# ESP32_AC_dimmer_10ch_r1.net
KiCad netlist of a schematic drawn in EAGLE
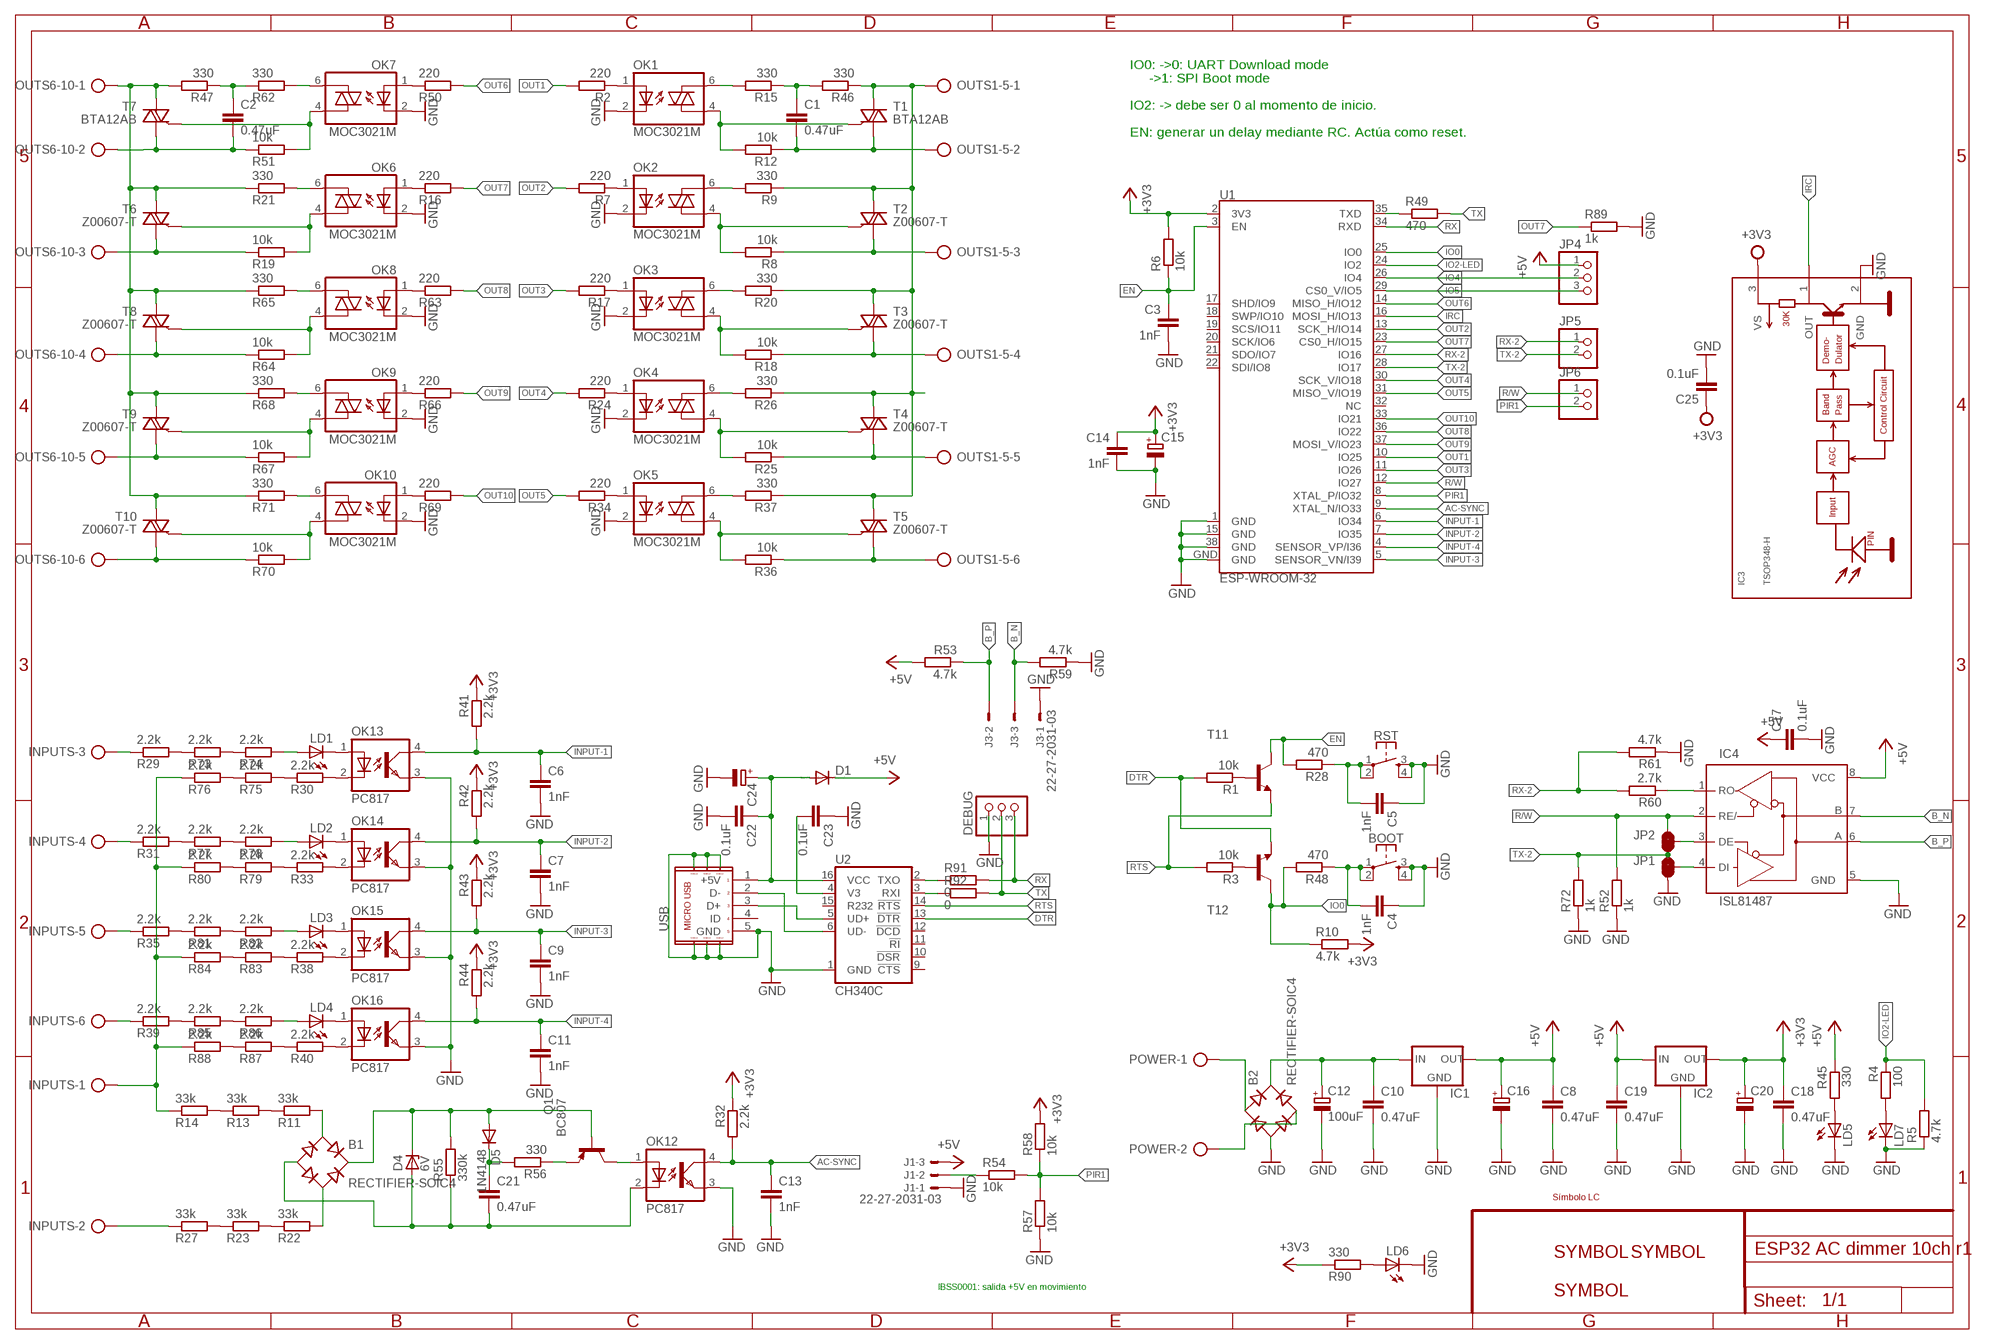
[diagram p0: schematic, sheet 1]

(export (version "E")
  (design (tool "Eeschema 10.0.6"))
  (components
    (comp (ref "B1")
      (value "RECTIFIER-SOIC4")
      (footprint "eagle-import:SOIC4")
      (libsource (lib "eagle-import") (part "RECTIFIER-SOIC4"))
    )
    (comp (ref "B2")
      (value "RECTIFIER-SOIC4")
      (footprint "eagle-import:SOIC4")
      (libsource (lib "eagle-import") (part "RECTIFIER-SOIC4"))
    )
    (comp (ref "BOOT")
      (value "MOMENTARY-SWITCH-SPST-2-SMD-4.6X2.8MM")
      (footprint "eagle-import:TACTILE_SWITCH_SMD_4.6X2.8MM")
      (libsource (lib "eagle-import") (part "MOMENTARY-SWITCH-SPST-2-SMD-4.6X2.8MM"))
    )
    (comp (ref "C1")
      (value "0.47uF")
      (footprint "eagle-import:C075-042X103")
      (libsource (lib "eagle-import") (part "C-EU075-042X103"))
    )
    (comp (ref "C2")
      (value "0.47uF")
      (footprint "eagle-import:C075-042X103")
      (libsource (lib "eagle-import") (part "C-EU075-042X103"))
    )
    (comp (ref "C3")
      (value "1nF")
      (footprint "eagle-import:C0603")
      (libsource (lib "eagle-import") (part "C-EUC0603"))
    )
    (comp (ref "C4")
      (value "1nF")
      (footprint "eagle-import:C0603")
      (libsource (lib "eagle-import") (part "C-EUC0603"))
    )
    (comp (ref "C5")
      (value "1nF")
      (footprint "eagle-import:C0603")
      (libsource (lib "eagle-import") (part "C-EUC0603"))
    )
    (comp (ref "C6")
      (value "1nF")
      (footprint "eagle-import:C0603")
      (libsource (lib "eagle-import") (part "C-EUC0603"))
    )
    (comp (ref "C7")
      (value "1nF")
      (footprint "eagle-import:C0603")
      (libsource (lib "eagle-import") (part "C-EUC0603"))
    )
    (comp (ref "C8")
      (value "0.47uF")
      (footprint "eagle-import:C0805")
      (libsource (lib "eagle-import") (part "C-EUC0805"))
    )
    (comp (ref "C9")
      (value "1nF")
      (footprint "eagle-import:C0603")
      (libsource (lib "eagle-import") (part "C-EUC0603"))
    )
    (comp (ref "C10")
      (value "0.47uF")
      (footprint "eagle-import:C0805")
      (libsource (lib "eagle-import") (part "C-EUC0805"))
    )
    (comp (ref "C11")
      (value "1nF")
      (footprint "eagle-import:C0603")
      (libsource (lib "eagle-import") (part "C-EUC0603"))
    )
    (comp (ref "C12")
      (value "100uF")
      (footprint "eagle-import:E3,5-8")
      (libsource (lib "eagle-import") (part "CPOL-EUE3.5-8"))
    )
    (comp (ref "C13")
      (value "1nF")
      (footprint "eagle-import:C0603")
      (libsource (lib "eagle-import") (part "C-EUC0603"))
    )
    (comp (ref "C14")
      (value "1nF")
      (footprint "eagle-import:C0805")
      (libsource (lib "eagle-import") (part "C-EUC0805"))
    )
    (comp (ref "C15")
      (value "CPOL-EUSMCA")
      (footprint "eagle-import:SMC_A")
      (libsource (lib "eagle-import") (part "rcl_334_CPOL-EUSMCA"))
    )
    (comp (ref "C16")
      (value "CPOL-EUSMCA")
      (footprint "eagle-import:SMC_A")
      (libsource (lib "eagle-import") (part "rcl_334_CPOL-EUSMCA"))
    )
    (comp (ref "C17")
      (value "0.1uF")
      (footprint "eagle-import:RCL_C0603")
      (libsource (lib "eagle-import") (part "RCL_C-EUC0603"))
    )
    (comp (ref "C18")
      (value "0.47uF")
      (footprint "eagle-import:C0805")
      (libsource (lib "eagle-import") (part "C-EUC0805"))
    )
    (comp (ref "C19")
      (value "0.47uF")
      (footprint "eagle-import:C0805")
      (libsource (lib "eagle-import") (part "C-EUC0805"))
    )
    (comp (ref "C20")
      (value "CPOL-EUSMCA")
      (footprint "eagle-import:SMC_A")
      (libsource (lib "eagle-import") (part "rcl_334_CPOL-EUSMCA"))
    )
    (comp (ref "C21")
      (value "0.47uF")
      (footprint "eagle-import:C0805")
      (libsource (lib "eagle-import") (part "C-EUC0805"))
    )
    (comp (ref "C22")
      (value "0.1uF")
      (footprint "eagle-import:C0603")
      (libsource (lib "eagle-import") (part "C-EUC0603"))
    )
    (comp (ref "C23")
      (value "0.1uF")
      (footprint "eagle-import:C0603")
      (libsource (lib "eagle-import") (part "C-EUC0603"))
    )
    (comp (ref "C24")
      (value "CPOL-EUSMCA")
      (footprint "eagle-import:SMC_A")
      (libsource (lib "eagle-import") (part "rcl_334_CPOL-EUSMCA"))
    )
    (comp (ref "C25")
      (value "0.1uF")
      (footprint "eagle-import:C0603")
      (libsource (lib "eagle-import") (part "C-EUC0603"))
    )
    (comp (ref "D1")
      (value "DIODE-SOD323-R")
      (footprint "eagle-import:SOD323-R")
      (libsource (lib "eagle-import") (part "diode_210_DIODE-SOD323-R"))
    )
    (comp (ref "D4")
      (value "6V")
      (footprint "eagle-import:SOD80C")
      (libsource (lib "eagle-import") (part "ZENER-DIODESOD80C"))
    )
    (comp (ref "D5")
      (value "1N4148")
      (footprint "eagle-import:MINIMELF")
      (libsource (lib "eagle-import") (part "DIODE-MINIMELF"))
    )
    (comp (ref "DEBUG")
      (value "PINHD-1X3")
      (footprint "eagle-import:1X03")
      (libsource (lib "eagle-import") (part "PINHD-1X3"))
    )
    (comp (ref "IC1")
      (value "LM1117")
      (footprint "eagle-import:SOT223")
      (libsource (lib "eagle-import") (part "LM1117"))
    )
    (comp (ref "IC2")
      (value "LM1117")
      (footprint "eagle-import:SOT223")
      (libsource (lib "eagle-import") (part "LM1117"))
    )
    (comp (ref "IC3")
      (value "TSOP348-H")
      (footprint "eagle-import:TSOP348H")
      (libsource (lib "eagle-import") (part "TSOP348-H"))
    )
    (comp (ref "IC4")
      (value "ISL81487")
      (footprint "eagle-import:MAXIM_SO08")
      (libsource (lib "eagle-import") (part "MAXIM_MAX34SA68C"))
    )
    (comp (ref "INPUTS")
      (value "AK500/6")
      (footprint "eagle-import:AK500_6")
      (libsource (lib "eagle-import") (part "AK500/6"))
    )
    (comp (ref "J1")
      (value "22-27-2031-03")
      (footprint "eagle-import:6410-03")
      (libsource (lib "eagle-import") (part "22-?-0327-2031"))
    )
    (comp (ref "J3")
      (value "22-27-2031-03")
      (footprint "eagle-import:6410-03")
      (libsource (lib "eagle-import") (part "22-?-0327-2031"))
    )
    (comp (ref "JP1")
      (value "JUMPER-SMT_3_1-NC_TRACE_SILK")
      (footprint "eagle-import:SMT-JUMPER_3_1-NC_TRACE_SILK")
      (libsource (lib "eagle-import") (part "JUMPER-SMT_3_1-NC_TRACE_SILK"))
    )
    (comp (ref "JP2")
      (value "JUMPER-SMT_3_1-NC_TRACE_SILK")
      (footprint "eagle-import:SMT-JUMPER_3_1-NC_TRACE_SILK")
      (libsource (lib "eagle-import") (part "JUMPER-SMT_3_1-NC_TRACE_SILK"))
    )
    (comp (ref "JP4")
      (value "PINHD-1X3")
      (footprint "eagle-import:1X03")
      (libsource (lib "eagle-import") (part "PINHD-1X3"))
    )
    (comp (ref "JP5")
      (value "PINHD-1X2")
      (footprint "eagle-import:1X02")
      (libsource (lib "eagle-import") (part "PINHD-1X2"))
    )
    (comp (ref "JP6")
      (value "PINHD-1X2")
      (footprint "eagle-import:1X02")
      (libsource (lib "eagle-import") (part "PINHD-1X2"))
    )
    (comp (ref "LD1")
      (value "LEDCHIPLED_0805")
      (footprint "eagle-import:CHIPLED_0805")
      (libsource (lib "eagle-import") (part "LEDCHIPLED_0805"))
    )
    (comp (ref "LD2")
      (value "LEDCHIPLED_0805")
      (footprint "eagle-import:CHIPLED_0805")
      (libsource (lib "eagle-import") (part "LEDCHIPLED_0805"))
    )
    (comp (ref "LD3")
      (value "LEDCHIPLED_0805")
      (footprint "eagle-import:CHIPLED_0805")
      (libsource (lib "eagle-import") (part "LEDCHIPLED_0805"))
    )
    (comp (ref "LD4")
      (value "LEDCHIPLED_0805")
      (footprint "eagle-import:CHIPLED_0805")
      (libsource (lib "eagle-import") (part "LEDCHIPLED_0805"))
    )
    (comp (ref "LD5")
      (value "LEDCHIPLED_0805")
      (footprint "eagle-import:CHIPLED_0805")
      (fields (field (name "SPICEPREFIX") "L"))
      (libsource (lib "eagle-import") (part "LEDCHIPLED_0805"))
    )
    (comp (ref "LD6")
      (value "LEDCHIPLED_0805")
      (footprint "eagle-import:CHIPLED_0805")
      (fields (field (name "SPICEPREFIX") "L"))
      (libsource (lib "eagle-import") (part "LEDCHIPLED_0805"))
    )
    (comp (ref "LD7")
      (value "LEDCHIPLED_0805")
      (footprint "eagle-import:CHIPLED_0805")
      (fields (field (name "SPICEPREFIX") "L"))
      (libsource (lib "eagle-import") (part "LEDCHIPLED_0805"))
    )
    (comp (ref "OK1")
      (value "MOC3021M")
      (footprint "eagle-import:DIL06")
      (libsource (lib "eagle-import") (part "MOC30M21"))
    )
    (comp (ref "OK2")
      (value "MOC3021M")
      (footprint "eagle-import:DIL06")
      (libsource (lib "eagle-import") (part "MOC30M21"))
    )
    (comp (ref "OK3")
      (value "MOC3021M")
      (footprint "eagle-import:DIL06")
      (libsource (lib "eagle-import") (part "MOC30M21"))
    )
    (comp (ref "OK4")
      (value "MOC3021M")
      (footprint "eagle-import:DIL06")
      (libsource (lib "eagle-import") (part "MOC30M21"))
    )
    (comp (ref "OK5")
      (value "MOC3021M")
      (footprint "eagle-import:DIL06")
      (libsource (lib "eagle-import") (part "MOC30M21"))
    )
    (comp (ref "OK6")
      (value "MOC3021M")
      (footprint "eagle-import:DIL06")
      (libsource (lib "eagle-import") (part "MOC30M21"))
    )
    (comp (ref "OK7")
      (value "MOC3021M")
      (footprint "eagle-import:DIL06")
      (libsource (lib "eagle-import") (part "MOC30M21"))
    )
    (comp (ref "OK8")
      (value "MOC3021M")
      (footprint "eagle-import:DIL06")
      (libsource (lib "eagle-import") (part "MOC30M21"))
    )
    (comp (ref "OK9")
      (value "MOC3021M")
      (footprint "eagle-import:DIL06")
      (libsource (lib "eagle-import") (part "MOC30M21"))
    )
    (comp (ref "OK10")
      (value "MOC3021M")
      (footprint "eagle-import:DIL06")
      (libsource (lib "eagle-import") (part "MOC30M21"))
    )
    (comp (ref "OK12")
      (value "PC817")
      (footprint "eagle-import:DIL04")
      (libsource (lib "eagle-import") (part "PC817"))
    )
    (comp (ref "OK13")
      (value "PC817")
      (footprint "eagle-import:DIL04")
      (libsource (lib "eagle-import") (part "PC817"))
    )
    (comp (ref "OK14")
      (value "PC817")
      (footprint "eagle-import:DIL04")
      (libsource (lib "eagle-import") (part "PC817"))
    )
    (comp (ref "OK15")
      (value "PC817")
      (footprint "eagle-import:DIL04")
      (libsource (lib "eagle-import") (part "PC817"))
    )
    (comp (ref "OK16")
      (value "PC817")
      (footprint "eagle-import:DIL04")
      (libsource (lib "eagle-import") (part "PC817"))
    )
    (comp (ref "OUTS1-5")
      (value "AK500/6")
      (footprint "eagle-import:AK500_6")
      (libsource (lib "eagle-import") (part "AK500/6"))
    )
    (comp (ref "OUTS6-10")
      (value "AK500/6")
      (footprint "eagle-import:AK500_6")
      (libsource (lib "eagle-import") (part "AK500/6"))
    )
    (comp (ref "POWER")
      (value "AK500/2")
      (footprint "eagle-import:AK500_2")
      (libsource (lib "eagle-import") (part "AK500/2"))
    )
    (comp (ref "Q1")
      (value "BC807")
      (footprint "eagle-import:SOT23-BEC")
      (libsource (lib "eagle-import") (part "-PNP-SOT23-BECBC807-25"))
    )
    (comp (ref "R1")
      (value "10k")
      (footprint "eagle-import:R0603")
      (libsource (lib "eagle-import") (part "R-EU_R0603"))
    )
    (comp (ref "R2")
      (value "220")
      (footprint "eagle-import:R0603")
      (libsource (lib "eagle-import") (part "R-EU_R0603"))
    )
    (comp (ref "R3")
      (value "10k")
      (footprint "eagle-import:R0603")
      (libsource (lib "eagle-import") (part "R-EU_R0603"))
    )
    (comp (ref "R4")
      (value "100")
      (footprint "eagle-import:R0603")
      (fields (field (name "SPICEPREFIX") "R"))
      (libsource (lib "eagle-import") (part "R-EU_R0603"))
    )
    (comp (ref "R5")
      (value "4.7k")
      (footprint "eagle-import:R0603")
      (libsource (lib "eagle-import") (part "R-EU_R0603"))
    )
    (comp (ref "R6")
      (value "10k")
      (footprint "eagle-import:R0603")
      (libsource (lib "eagle-import") (part "R-EU_R0603"))
    )
    (comp (ref "R7")
      (value "220")
      (footprint "eagle-import:R0603")
      (libsource (lib "eagle-import") (part "R-EU_R0603"))
    )
    (comp (ref "R8")
      (value "10k")
      (footprint "eagle-import:0204_5")
      (libsource (lib "eagle-import") (part "R-EU_0204/5"))
    )
    (comp (ref "R9")
      (value "330")
      (footprint "eagle-import:0204_5")
      (libsource (lib "eagle-import") (part "R-EU_0204/5"))
    )
    (comp (ref "R10")
      (value "4.7k")
      (footprint "eagle-import:R0603")
      (libsource (lib "eagle-import") (part "R-EU_R0603"))
    )
    (comp (ref "R11")
      (value "33k")
      (footprint "eagle-import:R0805")
      (libsource (lib "eagle-import") (part "R-EU_R0805"))
    )
    (comp (ref "R12")
      (value "10k")
      (footprint "eagle-import:0204_5")
      (libsource (lib "eagle-import") (part "R-EU_0204/5"))
    )
    (comp (ref "R13")
      (value "33k")
      (footprint "eagle-import:R0805")
      (libsource (lib "eagle-import") (part "R-EU_R0805"))
    )
    (comp (ref "R14")
      (value "33k")
      (footprint "eagle-import:R0805")
      (libsource (lib "eagle-import") (part "R-EU_R0805"))
    )
    (comp (ref "R15")
      (value "330")
      (footprint "eagle-import:0204_5")
      (libsource (lib "eagle-import") (part "R-EU_0204/5"))
    )
    (comp (ref "R16")
      (value "220")
      (footprint "eagle-import:R0603")
      (libsource (lib "eagle-import") (part "R-EU_R0603"))
    )
    (comp (ref "R17")
      (value "220")
      (footprint "eagle-import:R0603")
      (libsource (lib "eagle-import") (part "R-EU_R0603"))
    )
    (comp (ref "R18")
      (value "10k")
      (footprint "eagle-import:0204_5")
      (libsource (lib "eagle-import") (part "R-EU_0204/5"))
    )
    (comp (ref "R19")
      (value "10k")
      (footprint "eagle-import:0204_5")
      (libsource (lib "eagle-import") (part "R-EU_0204/5"))
    )
    (comp (ref "R20")
      (value "330")
      (footprint "eagle-import:0204_5")
      (libsource (lib "eagle-import") (part "R-EU_0204/5"))
    )
    (comp (ref "R21")
      (value "330")
      (footprint "eagle-import:0204_5")
      (libsource (lib "eagle-import") (part "R-EU_0204/5"))
    )
    (comp (ref "R22")
      (value "33k")
      (footprint "eagle-import:R0805")
      (libsource (lib "eagle-import") (part "R-EU_R0805"))
    )
    (comp (ref "R23")
      (value "33k")
      (footprint "eagle-import:R0805")
      (libsource (lib "eagle-import") (part "R-EU_R0805"))
    )
    (comp (ref "R24")
      (value "220")
      (footprint "eagle-import:R0603")
      (libsource (lib "eagle-import") (part "R-EU_R0603"))
    )
    (comp (ref "R25")
      (value "10k")
      (footprint "eagle-import:0204_5")
      (libsource (lib "eagle-import") (part "R-EU_0204/5"))
    )
    (comp (ref "R26")
      (value "330")
      (footprint "eagle-import:0204_5")
      (libsource (lib "eagle-import") (part "R-EU_0204/5"))
    )
    (comp (ref "R27")
      (value "33k")
      (footprint "eagle-import:R0805")
      (libsource (lib "eagle-import") (part "R-EU_R0805"))
    )
    (comp (ref "R28")
      (value "470")
      (footprint "eagle-import:R0603")
      (libsource (lib "eagle-import") (part "R-EU_R0603"))
    )
    (comp (ref "R29")
      (value "2.2k")
      (footprint "eagle-import:R0805")
      (libsource (lib "eagle-import") (part "R-EU_R0805"))
    )
    (comp (ref "R30")
      (value "2.2k")
      (footprint "eagle-import:R0805")
      (libsource (lib "eagle-import") (part "R-EU_R0805"))
    )
    (comp (ref "R31")
      (value "2.2k")
      (footprint "eagle-import:R0805")
      (libsource (lib "eagle-import") (part "R-EU_R0805"))
    )
    (comp (ref "R32")
      (value "2.2k")
      (footprint "eagle-import:R0603")
      (libsource (lib "eagle-import") (part "R-EU_R0603"))
    )
    (comp (ref "R33")
      (value "2.2k")
      (footprint "eagle-import:R0805")
      (libsource (lib "eagle-import") (part "R-EU_R0805"))
    )
    (comp (ref "R34")
      (value "220")
      (footprint "eagle-import:R0603")
      (libsource (lib "eagle-import") (part "R-EU_R0603"))
    )
    (comp (ref "R35")
      (value "2.2k")
      (footprint "eagle-import:R0805")
      (libsource (lib "eagle-import") (part "R-EU_R0805"))
    )
    (comp (ref "R36")
      (value "10k")
      (footprint "eagle-import:0204_5")
      (libsource (lib "eagle-import") (part "R-EU_0204/5"))
    )
    (comp (ref "R37")
      (value "330")
      (footprint "eagle-import:0204_5")
      (libsource (lib "eagle-import") (part "R-EU_0204/5"))
    )
    (comp (ref "R38")
      (value "2.2k")
      (footprint "eagle-import:R0805")
      (libsource (lib "eagle-import") (part "R-EU_R0805"))
    )
    (comp (ref "R39")
      (value "2.2k")
      (footprint "eagle-import:R0805")
      (libsource (lib "eagle-import") (part "R-EU_R0805"))
    )
    (comp (ref "R40")
      (value "2.2k")
      (footprint "eagle-import:R0805")
      (libsource (lib "eagle-import") (part "R-EU_R0805"))
    )
    (comp (ref "R41")
      (value "2.2k")
      (footprint "eagle-import:R0603")
      (libsource (lib "eagle-import") (part "R-EU_R0603"))
    )
    (comp (ref "R42")
      (value "2.2k")
      (footprint "eagle-import:R0603")
      (libsource (lib "eagle-import") (part "R-EU_R0603"))
    )
    (comp (ref "R43")
      (value "2.2k")
      (footprint "eagle-import:R0603")
      (libsource (lib "eagle-import") (part "R-EU_R0603"))
    )
    (comp (ref "R44")
      (value "2.2k")
      (footprint "eagle-import:R0603")
      (libsource (lib "eagle-import") (part "R-EU_R0603"))
    )
    (comp (ref "R45")
      (value "330")
      (footprint "eagle-import:R0603")
      (fields (field (name "SPICEPREFIX") "R"))
      (libsource (lib "eagle-import") (part "R-EU_R0603"))
    )
    (comp (ref "R46")
      (value "330")
      (footprint "eagle-import:0204_7")
      (libsource (lib "eagle-import") (part "R-EU_0204/7"))
    )
    (comp (ref "R47")
      (value "330")
      (footprint "eagle-import:0204_7")
      (libsource (lib "eagle-import") (part "R-EU_0204/7"))
    )
    (comp (ref "R48")
      (value "470")
      (footprint "eagle-import:R0603")
      (libsource (lib "eagle-import") (part "R-EU_R0603"))
    )
    (comp (ref "R49")
      (value "470")
      (footprint "eagle-import:R0603")
      (libsource (lib "eagle-import") (part "R-EU_R0603"))
    )
    (comp (ref "R50")
      (value "220")
      (footprint "eagle-import:R0603")
      (libsource (lib "eagle-import") (part "R-EU_R0603"))
    )
    (comp (ref "R51")
      (value "10k")
      (footprint "eagle-import:0204_5")
      (libsource (lib "eagle-import") (part "R-EU_0204/5"))
    )
    (comp (ref "R52")
      (value "1k")
      (footprint "eagle-import:R0603")
      (libsource (lib "eagle-import") (part "R-EU_R0603"))
    )
    (comp (ref "R53")
      (value "4.7k")
      (footprint "eagle-import:R0603")
      (libsource (lib "eagle-import") (part "R-EU_R0603"))
    )
    (comp (ref "R54")
      (value "10k")
      (footprint "eagle-import:R0603")
      (libsource (lib "eagle-import") (part "R-EU_R0603"))
    )
    (comp (ref "R55")
      (value "330k")
      (footprint "eagle-import:R0805")
      (libsource (lib "eagle-import") (part "R-EU_R0805"))
    )
    (comp (ref "R56")
      (value "330")
      (footprint "eagle-import:R0805")
      (libsource (lib "eagle-import") (part "R-EU_R0805"))
    )
    (comp (ref "R57")
      (value "10k")
      (footprint "eagle-import:R0603")
      (libsource (lib "eagle-import") (part "R-EU_R0603"))
    )
    (comp (ref "R58")
      (value "10k")
      (footprint "eagle-import:R0603")
      (libsource (lib "eagle-import") (part "R-EU_R0603"))
    )
    (comp (ref "R59")
      (value "4.7k")
      (footprint "eagle-import:R0603")
      (libsource (lib "eagle-import") (part "R-EU_R0603"))
    )
    (comp (ref "R60")
      (value "2.7k")
      (footprint "eagle-import:R0603")
      (libsource (lib "eagle-import") (part "R-EU_R0603"))
    )
    (comp (ref "R61")
      (value "4.7k")
      (footprint "eagle-import:R0603")
      (libsource (lib "eagle-import") (part "R-EU_R0603"))
    )
    (comp (ref "R62")
      (value "330")
      (footprint "eagle-import:0204_5")
      (libsource (lib "eagle-import") (part "R-EU_0204/5"))
    )
    (comp (ref "R63")
      (value "220")
      (footprint "eagle-import:R0603")
      (libsource (lib "eagle-import") (part "R-EU_R0603"))
    )
    (comp (ref "R64")
      (value "10k")
      (footprint "eagle-import:0204_5")
      (libsource (lib "eagle-import") (part "R-EU_0204/5"))
    )
    (comp (ref "R65")
      (value "330")
      (footprint "eagle-import:0204_5")
      (libsource (lib "eagle-import") (part "R-EU_0204/5"))
    )
    (comp (ref "R66")
      (value "220")
      (footprint "eagle-import:R0603")
      (libsource (lib "eagle-import") (part "R-EU_R0603"))
    )
    (comp (ref "R67")
      (value "10k")
      (footprint "eagle-import:0204_5")
      (libsource (lib "eagle-import") (part "R-EU_0204/5"))
    )
    (comp (ref "R68")
      (value "330")
      (footprint "eagle-import:0204_5")
      (libsource (lib "eagle-import") (part "R-EU_0204/5"))
    )
    (comp (ref "R69")
      (value "220")
      (footprint "eagle-import:R0603")
      (libsource (lib "eagle-import") (part "R-EU_R0603"))
    )
    (comp (ref "R70")
      (value "10k")
      (footprint "eagle-import:0204_5")
      (libsource (lib "eagle-import") (part "R-EU_0204/5"))
    )
    (comp (ref "R71")
      (value "330")
      (footprint "eagle-import:0204_5")
      (libsource (lib "eagle-import") (part "R-EU_0204/5"))
    )
    (comp (ref "R72")
      (value "1k")
      (footprint "eagle-import:R0603")
      (libsource (lib "eagle-import") (part "R-EU_R0603"))
    )
    (comp (ref "R73")
      (value "2.2k")
      (footprint "eagle-import:R0805")
      (libsource (lib "eagle-import") (part "R-EU_R0805"))
    )
    (comp (ref "R74")
      (value "2.2k")
      (footprint "eagle-import:R0805")
      (libsource (lib "eagle-import") (part "R-EU_R0805"))
    )
    (comp (ref "R75")
      (value "2.2k")
      (footprint "eagle-import:R0805")
      (libsource (lib "eagle-import") (part "R-EU_R0805"))
    )
    (comp (ref "R76")
      (value "2.2k")
      (footprint "eagle-import:R0805")
      (libsource (lib "eagle-import") (part "R-EU_R0805"))
    )
    (comp (ref "R77")
      (value "2.2k")
      (footprint "eagle-import:R0805")
      (libsource (lib "eagle-import") (part "R-EU_R0805"))
    )
    (comp (ref "R78")
      (value "2.2k")
      (footprint "eagle-import:R0805")
      (libsource (lib "eagle-import") (part "R-EU_R0805"))
    )
    (comp (ref "R79")
      (value "2.2k")
      (footprint "eagle-import:R0805")
      (libsource (lib "eagle-import") (part "R-EU_R0805"))
    )
    (comp (ref "R80")
      (value "2.2k")
      (footprint "eagle-import:R0805")
      (libsource (lib "eagle-import") (part "R-EU_R0805"))
    )
    (comp (ref "R81")
      (value "2.2k")
      (footprint "eagle-import:R0805")
      (libsource (lib "eagle-import") (part "R-EU_R0805"))
    )
    (comp (ref "R82")
      (value "2.2k")
      (footprint "eagle-import:R0805")
      (libsource (lib "eagle-import") (part "R-EU_R0805"))
    )
    (comp (ref "R83")
      (value "2.2k")
      (footprint "eagle-import:R0805")
      (libsource (lib "eagle-import") (part "R-EU_R0805"))
    )
    (comp (ref "R84")
      (value "2.2k")
      (footprint "eagle-import:R0805")
      (libsource (lib "eagle-import") (part "R-EU_R0805"))
    )
    (comp (ref "R85")
      (value "2.2k")
      (footprint "eagle-import:R0805")
      (libsource (lib "eagle-import") (part "R-EU_R0805"))
    )
    (comp (ref "R86")
      (value "2.2k")
      (footprint "eagle-import:R0805")
      (libsource (lib "eagle-import") (part "R-EU_R0805"))
    )
    (comp (ref "R87")
      (value "2.2k")
      (footprint "eagle-import:R0805")
      (libsource (lib "eagle-import") (part "R-EU_R0805"))
    )
    (comp (ref "R88")
      (value "2.2k")
      (footprint "eagle-import:R0805")
      (libsource (lib "eagle-import") (part "R-EU_R0805"))
    )
    (comp (ref "R89")
      (value "1k")
      (footprint "eagle-import:R0603")
      (libsource (lib "eagle-import") (part "R-EU_R0603"))
    )
    (comp (ref "R90")
      (value "330")
      (footprint "eagle-import:R0603")
      (fields (field (name "SPICEPREFIX") "R"))
      (libsource (lib "eagle-import") (part "R-EU_R0603"))
    )
    (comp (ref "R91")
      (value "0")
      (footprint "eagle-import:R0603")
      (libsource (lib "eagle-import") (part "R-EU_R0603"))
    )
    (comp (ref "R92")
      (value "0")
      (footprint "eagle-import:R0603")
      (libsource (lib "eagle-import") (part "R-EU_R0603"))
    )
    (comp (ref "RST")
      (value "MOMENTARY-SWITCH-SPST-2-SMD-4.6X2.8MM")
      (footprint "eagle-import:TACTILE_SWITCH_SMD_4.6X2.8MM")
      (libsource (lib "eagle-import") (part "MOMENTARY-SWITCH-SPST-2-SMD-4.6X2.8MM"))
    )
    (comp (ref "SYM1")
      (value "LC-3.81")
      (footprint "eagle-import:LC_3.81MM")
      (libsource (lib "eagle-import") (part "LC-3.81"))
    )
    (comp (ref "T1")
      (value "BTA12AB")
      (footprint "eagle-import:TO220DS")
      (libsource (lib "eagle-import") (part "BTA12AB"))
    )
    (comp (ref "T2")
      (value "Z00607-T")
      (footprint "eagle-import:TO92-A1GA2")
      (libsource (lib "eagle-import") (part "Z00607-T"))
    )
    (comp (ref "T3")
      (value "Z00607-T")
      (footprint "eagle-import:TO92-A1GA2")
      (libsource (lib "eagle-import") (part "Z00607-T"))
    )
    (comp (ref "T4")
      (value "Z00607-T")
      (footprint "eagle-import:TO92-A1GA2")
      (libsource (lib "eagle-import") (part "Z00607-T"))
    )
    (comp (ref "T5")
      (value "Z00607-T")
      (footprint "eagle-import:TO92-A1GA2")
      (libsource (lib "eagle-import") (part "Z00607-T"))
    )
    (comp (ref "T6")
      (value "Z00607-T")
      (footprint "eagle-import:TO92-A1GA2")
      (libsource (lib "eagle-import") (part "Z00607-T"))
    )
    (comp (ref "T7")
      (value "BTA12AB")
      (footprint "eagle-import:TO220DS")
      (libsource (lib "eagle-import") (part "BTA12AB"))
    )
    (comp (ref "T8")
      (value "Z00607-T")
      (footprint "eagle-import:TO92-A1GA2")
      (libsource (lib "eagle-import") (part "Z00607-T"))
    )
    (comp (ref "T9")
      (value "Z00607-T")
      (footprint "eagle-import:TO92-A1GA2")
      (libsource (lib "eagle-import") (part "Z00607-T"))
    )
    (comp (ref "T10")
      (value "Z00607-T")
      (footprint "eagle-import:TO92-A1GA2")
      (libsource (lib "eagle-import") (part "Z00607-T"))
    )
    (comp (ref "T11")
      (value "BC817-16-NPN-SOT23-BEC")
      (footprint "eagle-import:SOT23-BEC")
      (libsource (lib "eagle-import") (part "-NPN-SOT23-BECBC817-16"))
    )
    (comp (ref "T12")
      (value "BC817-16-NPN-SOT23-BEC")
      (footprint "eagle-import:SOT23-BEC")
      (libsource (lib "eagle-import") (part "-NPN-SOT23-BECBC817-16"))
    )
    (comp (ref "U$1")
      (value "SYMBOLS")
      (footprint "eagle-import:WIFI_SYM")
      (libsource (lib "eagle-import") (part "SYMBOLS"))
    )
    (comp (ref "U$2")
      (value "SYMBOLS")
      (footprint "eagle-import:WIFI_SYM")
      (libsource (lib "eagle-import") (part "SYMBOLS"))
    )
    (comp (ref "U$3")
      (value "SYMBOLS-1")
      (footprint "eagle-import:WIFI-SYM2")
      (libsource (lib "eagle-import") (part "SYMBOLS-1"))
    )
    (comp (ref "U1")
      (value "ESP-WROOM-32")
      (footprint "eagle-import:ESP-WROOM-32")
      (libsource (lib "eagle-import") (part "ESP-WROOM-32"))
    )
    (comp (ref "U2")
      (value "CH340C")
      (footprint "eagle-import:SO016")
      (libsource (lib "eagle-import") (part "CH340C"))
    )
    (comp (ref "USB")
      (value "MICROUSB-LP")
      (footprint "eagle-import:MICROUSB-4PIN-LONGPIN")
      (libsource (lib "eagle-import") (part "MICROUSB-LP"))
    )
  )
  (nets
    (net (code "1") (name "+3V3") (class "Default")
      (node (ref "C14") (pin "1") (pinfunction "1_1") (pintype "passive"))
      (node (ref "C15") (pin "+") (pinfunction "+_+") (pintype "passive"))
      (node (ref "C18") (pin "1") (pinfunction "1_1") (pintype "passive"))
      (node (ref "C20") (pin "+") (pinfunction "+_+") (pintype "passive"))
      (node (ref "C25") (pin "1") (pinfunction "1_1") (pintype "passive"))
      (node (ref "IC2") (pin "2") (pinfunction "OUT_2") (pintype "passive"))
      (node (ref "IC3") (pin "3") (pinfunction "VS_3") (pintype "power_in"))
      (node (ref "R10") (pin "2") (pinfunction "2_2") (pintype "passive"))
      (node (ref "R32") (pin "1") (pinfunction "1_1") (pintype "passive"))
      (node (ref "R41") (pin "1") (pinfunction "1_1") (pintype "passive"))
      (node (ref "R42") (pin "1") (pinfunction "1_1") (pintype "passive"))
      (node (ref "R43") (pin "1") (pinfunction "1_1") (pintype "passive"))
      (node (ref "R44") (pin "1") (pinfunction "1_1") (pintype "passive"))
      (node (ref "R58") (pin "2") (pinfunction "2_2") (pintype "passive"))
      (node (ref "R6") (pin "2") (pinfunction "2_2") (pintype "passive"))
      (node (ref "R90") (pin "1") (pinfunction "1_1") (pintype "passive"))
      (node (ref "U1") (pin "2") (pinfunction "3V3_2") (pintype "bidirectional"))
    )
    (net (code "2") (name "+5V") (class "Default")
      (node (ref "C16") (pin "+") (pinfunction "+_+") (pintype "passive"))
      (node (ref "C17") (pin "1") (pinfunction "1_1") (pintype "passive"))
      (node (ref "C19") (pin "1") (pinfunction "1_1") (pintype "passive"))
      (node (ref "C8") (pin "1") (pinfunction "1_1") (pintype "passive"))
      (node (ref "D1") (pin "C") (pinfunction "C_C") (pintype "passive"))
      (node (ref "IC1") (pin "2") (pinfunction "OUT_2") (pintype "passive"))
      (node (ref "IC2") (pin "3") (pinfunction "IN_3") (pintype "input"))
      (node (ref "IC4") (pin "8") (pinfunction "VCC_8") (pintype "power_in"))
      (node (ref "J1") (pin "3") (pinfunction "S_3") (pintype "passive"))
      (node (ref "JP4") (pin "1") (pinfunction "1_1") (pintype "passive"))
      (node (ref "R45") (pin "1") (pinfunction "1_1") (pintype "passive"))
      (node (ref "R53") (pin "2") (pinfunction "2_2") (pintype "passive"))
    )
    (net (code "3") (name "AC-SYNC") (class "Default")
      (node (ref "C13") (pin "1") (pinfunction "1_1") (pintype "passive"))
      (node (ref "OK12") (pin "4") (pinfunction "COL_4") (pintype "passive"))
      (node (ref "R32") (pin "2") (pinfunction "2_2") (pintype "passive"))
      (node (ref "U1") (pin "9") (pinfunction "XTAL_N/IO33_9") (pintype "bidirectional"))
    )
    (net (code "4") (name "B_N") (class "Default")
      (node (ref "IC4") (pin "7") (pinfunction "B_7") (pintype "passive"))
      (node (ref "J3") (pin "3") (pinfunction "S_3") (pintype "passive"))
      (node (ref "R59") (pin "2") (pinfunction "2_2") (pintype "passive"))
    )
    (net (code "5") (name "B_P") (class "Default")
      (node (ref "IC4") (pin "6") (pinfunction "A_6") (pintype "passive"))
      (node (ref "J3") (pin "2") (pinfunction "S_2") (pintype "passive"))
      (node (ref "R53") (pin "1") (pinfunction "1_1") (pintype "passive"))
    )
    (net (code "6") (name "DTR") (class "Default")
      (node (ref "R1") (pin "2") (pinfunction "2_2") (pintype "passive"))
      (node (ref "T12") (pin "E") (pinfunction "E_E") (pintype "passive"))
      (node (ref "U2") (pin "13") (pinfunction "~{DTR}_13") (pintype "bidirectional"))
    )
    (net (code "7") (name "EN") (class "Default")
      (node (ref "C3") (pin "1") (pinfunction "1_1") (pintype "passive"))
      (node (ref "R28") (pin "2") (pinfunction "2_2") (pintype "passive"))
      (node (ref "R6") (pin "1") (pinfunction "1_1") (pintype "passive"))
      (node (ref "T11") (pin "C") (pinfunction "C_C") (pintype "passive"))
      (node (ref "U1") (pin "3") (pinfunction "EN_3") (pintype "bidirectional"))
    )
    (net (code "8") (name "GND") (class "Default")
      (node (ref "B2") (pin "-") (pinfunction "-_-") (pintype "passive"))
      (node (ref "BOOT") (pin "3") (pinfunction "3_3") (pintype "passive"))
      (node (ref "BOOT") (pin "4") (pinfunction "4_4") (pintype "passive"))
      (node (ref "C10") (pin "2") (pinfunction "2_2") (pintype "passive"))
      (node (ref "C11") (pin "2") (pinfunction "2_2") (pintype "passive"))
      (node (ref "C12") (pin "-") (pinfunction "-_-") (pintype "passive"))
      (node (ref "C13") (pin "2") (pinfunction "2_2") (pintype "passive"))
      (node (ref "C14") (pin "2") (pinfunction "2_2") (pintype "passive"))
      (node (ref "C15") (pin "-") (pinfunction "-_-") (pintype "passive"))
      (node (ref "C16") (pin "-") (pinfunction "-_-") (pintype "passive"))
      (node (ref "C17") (pin "2") (pinfunction "2_2") (pintype "passive"))
      (node (ref "C18") (pin "2") (pinfunction "2_2") (pintype "passive"))
      (node (ref "C19") (pin "2") (pinfunction "2_2") (pintype "passive"))
      (node (ref "C20") (pin "-") (pinfunction "-_-") (pintype "passive"))
      (node (ref "C22") (pin "2") (pinfunction "2_2") (pintype "passive"))
      (node (ref "C23") (pin "1") (pinfunction "1_1") (pintype "passive"))
      (node (ref "C24") (pin "-") (pinfunction "-_-") (pintype "passive"))
      (node (ref "C25") (pin "2") (pinfunction "2_2") (pintype "passive"))
      (node (ref "C3") (pin "2") (pinfunction "2_2") (pintype "passive"))
      (node (ref "C4") (pin "1") (pinfunction "1_1") (pintype "passive"))
      (node (ref "C5") (pin "1") (pinfunction "1_1") (pintype "passive"))
      (node (ref "C6") (pin "2") (pinfunction "2_2") (pintype "passive"))
      (node (ref "C7") (pin "2") (pinfunction "2_2") (pintype "passive"))
      (node (ref "C8") (pin "2") (pinfunction "2_2") (pintype "passive"))
      (node (ref "C9") (pin "2") (pinfunction "2_2") (pintype "passive"))
      (node (ref "DEBUG") (pin "1") (pinfunction "1_1") (pintype "passive"))
      (node (ref "IC1") (pin "1") (pinfunction "GND_1") (pintype "input"))
      (node (ref "IC2") (pin "1") (pinfunction "GND_1") (pintype "input"))
      (node (ref "IC3") (pin "2") (pinfunction "GND_2") (pintype "power_in"))
      (node (ref "IC4") (pin "5") (pinfunction "GND_5") (pintype "power_in"))
      (node (ref "J1") (pin "1") (pinfunction "S_1") (pintype "passive"))
      (node (ref "J3") (pin "1") (pinfunction "S_1") (pintype "passive"))
      (node (ref "JP1") (pin "3") (pinfunction "3_3") (pintype "passive"))
      (node (ref "LD5") (pin "C") (pinfunction "C_C") (pintype "passive"))
      (node (ref "LD6") (pin "C") (pinfunction "C_C") (pintype "passive"))
      (node (ref "LD7") (pin "C") (pinfunction "C_C") (pintype "passive"))
      (node (ref "OK1") (pin "2") (pinfunction "C_2") (pintype "passive"))
      (node (ref "OK10") (pin "2") (pinfunction "C_2") (pintype "passive"))
      (node (ref "OK12") (pin "3") (pinfunction "EMIT_3") (pintype "passive"))
      (node (ref "OK13") (pin "3") (pinfunction "EMIT_3") (pintype "passive"))
      (node (ref "OK14") (pin "3") (pinfunction "EMIT_3") (pintype "passive"))
      (node (ref "OK15") (pin "3") (pinfunction "EMIT_3") (pintype "passive"))
      (node (ref "OK16") (pin "3") (pinfunction "EMIT_3") (pintype "passive"))
      (node (ref "OK2") (pin "2") (pinfunction "C_2") (pintype "passive"))
      (node (ref "OK3") (pin "2") (pinfunction "C_2") (pintype "passive"))
      (node (ref "OK4") (pin "2") (pinfunction "C_2") (pintype "passive"))
      (node (ref "OK5") (pin "2") (pinfunction "C_2") (pintype "passive"))
      (node (ref "OK6") (pin "2") (pinfunction "C_2") (pintype "passive"))
      (node (ref "OK7") (pin "2") (pinfunction "C_2") (pintype "passive"))
      (node (ref "OK8") (pin "2") (pinfunction "C_2") (pintype "passive"))
      (node (ref "OK9") (pin "2") (pinfunction "C_2") (pintype "passive"))
      (node (ref "R5") (pin "1") (pinfunction "1_1") (pintype "passive"))
      (node (ref "R52") (pin "1") (pinfunction "1_1") (pintype "passive"))
      (node (ref "R57") (pin "1") (pinfunction "1_1") (pintype "passive"))
      (node (ref "R59") (pin "1") (pinfunction "1_1") (pintype "passive"))
      (node (ref "R61") (pin "1") (pinfunction "1_1") (pintype "passive"))
      (node (ref "R72") (pin "1") (pinfunction "1_1") (pintype "passive"))
      (node (ref "R89") (pin "2") (pinfunction "2_2") (pintype "passive"))
      (node (ref "RST") (pin "3") (pinfunction "3_3") (pintype "passive"))
      (node (ref "RST") (pin "4") (pinfunction "4_4") (pintype "passive"))
      (node (ref "U1") (pin "1") (pinfunction "GND_1") (pintype "bidirectional"))
      (node (ref "U1") (pin "15") (pinfunction "GND_15") (pintype "bidirectional"))
      (node (ref "U1") (pin "38") (pinfunction "GND_38") (pintype "bidirectional"))
      (node (ref "U1") (pin "GND") (pinfunction "GND_GND") (pintype "bidirectional"))
      (node (ref "U2") (pin "1") (pinfunction "GND_1") (pintype "bidirectional"))
      (node (ref "USB") (pin "5") (pinfunction "GND_5") (pintype "bidirectional"))
      (node (ref "USB") (pin "P1") (pinfunction "P1_P1") (pintype "bidirectional"))
      (node (ref "USB") (pin "P2") (pinfunction "P2_P2") (pintype "bidirectional"))
      (node (ref "USB") (pin "P3") (pinfunction "P3_P3") (pintype "bidirectional"))
      (node (ref "USB") (pin "P4") (pinfunction "P4_P4") (pintype "bidirectional"))
      (node (ref "USB") (pin "P5") (pinfunction "P5_P5") (pintype "bidirectional"))
      (node (ref "USB") (pin "P6") (pinfunction "P6_P6") (pintype "bidirectional"))
    )
    (net (code "9") (name "INPUT-1") (class "Default")
      (node (ref "C6") (pin "1") (pinfunction "1_1") (pintype "passive"))
      (node (ref "OK13") (pin "4") (pinfunction "COL_4") (pintype "passive"))
      (node (ref "R41") (pin "2") (pinfunction "2_2") (pintype "passive"))
      (node (ref "U1") (pin "6") (pinfunction "IO34_6") (pintype "bidirectional"))
    )
    (net (code "10") (name "INPUT-2") (class "Default")
      (node (ref "C7") (pin "1") (pinfunction "1_1") (pintype "passive"))
      (node (ref "OK14") (pin "4") (pinfunction "COL_4") (pintype "passive"))
      (node (ref "R42") (pin "2") (pinfunction "2_2") (pintype "passive"))
      (node (ref "U1") (pin "7") (pinfunction "IO35_7") (pintype "bidirectional"))
    )
    (net (code "11") (name "INPUT-3") (class "Default")
      (node (ref "C9") (pin "1") (pinfunction "1_1") (pintype "passive"))
      (node (ref "OK15") (pin "4") (pinfunction "COL_4") (pintype "passive"))
      (node (ref "R43") (pin "2") (pinfunction "2_2") (pintype "passive"))
      (node (ref "U1") (pin "5") (pinfunction "SENSOR_VN/I39_5") (pintype "bidirectional"))
    )
    (net (code "12") (name "INPUT-4") (class "Default")
      (node (ref "C11") (pin "1") (pinfunction "1_1") (pintype "passive"))
      (node (ref "OK16") (pin "4") (pinfunction "COL_4") (pintype "passive"))
      (node (ref "R44") (pin "2") (pinfunction "2_2") (pintype "passive"))
      (node (ref "U1") (pin "4") (pinfunction "SENSOR_VP/I36_4") (pintype "bidirectional"))
    )
    (net (code "13") (name "IO0") (class "Default")
      (node (ref "R10") (pin "1") (pinfunction "1_1") (pintype "passive"))
      (node (ref "R48") (pin "2") (pinfunction "2_2") (pintype "passive"))
      (node (ref "T12") (pin "C") (pinfunction "C_C") (pintype "passive"))
      (node (ref "U1") (pin "25") (pinfunction "IO0_25") (pintype "bidirectional"))
    )
    (net (code "14") (name "IO2-LED") (class "Default")
      (node (ref "R4") (pin "1") (pinfunction "1_1") (pintype "passive"))
      (node (ref "R5") (pin "2") (pinfunction "2_2") (pintype "passive"))
      (node (ref "U1") (pin "24") (pinfunction "IO2_24") (pintype "bidirectional"))
    )
    (net (code "15") (name "IO4") (class "Default")
      (node (ref "JP4") (pin "2") (pinfunction "2_2") (pintype "passive"))
      (node (ref "U1") (pin "26") (pinfunction "IO4_26") (pintype "bidirectional"))
    )
    (net (code "16") (name "IO5") (class "Default")
      (node (ref "JP4") (pin "3") (pinfunction "3_3") (pintype "passive"))
      (node (ref "U1") (pin "29") (pinfunction "CS0_V/IO5_29") (pintype "bidirectional"))
    )
    (net (code "17") (name "IRC") (class "Default")
      (node (ref "IC3") (pin "1") (pinfunction "OUT_1") (pintype "output"))
      (node (ref "U1") (pin "16") (pinfunction "MOSI_H/IO13_16") (pintype "bidirectional"))
    )
    (net (code "18") (name "Net-(B1-Pad+)") (class "Default")
      (node (ref "B1") (pin "+") (pinfunction "+_+") (pintype "passive"))
      (node (ref "D4") (pin "C") (pinfunction "C_C") (pintype "passive"))
      (node (ref "D5") (pin "A") (pinfunction "A_A") (pintype "passive"))
      (node (ref "Q1") (pin "B") (pinfunction "B_B") (pintype "passive"))
      (node (ref "R55") (pin "2") (pinfunction "2_2") (pintype "passive"))
    )
    (net (code "19") (name "Net-(B1-PadAC1)") (class "Default")
      (node (ref "B1") (pin "AC1") (pinfunction "AC1_AC1") (pintype "passive"))
      (node (ref "R11") (pin "2") (pinfunction "2_2") (pintype "passive"))
    )
    (net (code "20") (name "Net-(B1-PadAC2)") (class "Default")
      (node (ref "B1") (pin "AC2") (pinfunction "AC2_AC2") (pintype "passive"))
      (node (ref "R22") (pin "2") (pinfunction "2_2") (pintype "passive"))
    )
    (net (code "21") (name "Net-(BOOT-Pad1)") (class "Default")
      (node (ref "BOOT") (pin "1") (pinfunction "1_1") (pintype "passive"))
      (node (ref "BOOT") (pin "2") (pinfunction "2_2") (pintype "passive"))
      (node (ref "C4") (pin "2") (pinfunction "2_2") (pintype "passive"))
      (node (ref "R48") (pin "1") (pinfunction "1_1") (pintype "passive"))
    )
    (net (code "22") (name "Net-(C1-Pad1)") (class "Default")
      (node (ref "C1") (pin "1") (pinfunction "1_1") (pintype "passive"))
      (node (ref "R15") (pin "1") (pinfunction "1_1") (pintype "passive"))
      (node (ref "R46") (pin "2") (pinfunction "2_2") (pintype "passive"))
    )
    (net (code "23") (name "Net-(C2-Pad1)") (class "Default")
      (node (ref "C2") (pin "1") (pinfunction "1_1") (pintype "passive"))
      (node (ref "R47") (pin "1") (pinfunction "1_1") (pintype "passive"))
      (node (ref "R62") (pin "1") (pinfunction "1_1") (pintype "passive"))
    )
    (net (code "24") (name "Net-(C5-Pad2)") (class "Default")
      (node (ref "C5") (pin "2") (pinfunction "2_2") (pintype "passive"))
      (node (ref "R28") (pin "1") (pinfunction "1_1") (pintype "passive"))
      (node (ref "RST") (pin "1") (pinfunction "1_1") (pintype "passive"))
      (node (ref "RST") (pin "2") (pinfunction "2_2") (pintype "passive"))
    )
    (net (code "25") (name "Net-(C21-Pad1)") (class "Default")
      (node (ref "C21") (pin "1") (pinfunction "1_1") (pintype "passive"))
      (node (ref "D5") (pin "C") (pinfunction "C_C") (pintype "passive"))
      (node (ref "R56") (pin "2") (pinfunction "2_2") (pintype "passive"))
    )
    (net (code "26") (name "Net-(IC1-IN)") (class "Default")
      (node (ref "B2") (pin "+") (pinfunction "+_+") (pintype "passive"))
      (node (ref "C10") (pin "1") (pinfunction "1_1") (pintype "passive"))
      (node (ref "C12") (pin "+") (pinfunction "+_+") (pintype "passive"))
      (node (ref "IC1") (pin "3") (pinfunction "IN_3") (pintype "input"))
    )
    (net (code "27") (name "Net-(IC4-DE)") (class "Default")
      (node (ref "IC4") (pin "3") (pinfunction "DE_3") (pintype "input"))
      (node (ref "JP2") (pin "2") (pinfunction "2_2") (pintype "passive"))
    )
    (net (code "28") (name "Net-(IC4-DI)") (class "Default")
      (node (ref "IC4") (pin "4") (pinfunction "DI_4") (pintype "input"))
      (node (ref "JP1") (pin "2") (pinfunction "2_2") (pintype "passive"))
    )
    (net (code "29") (name "Net-(IC4-RO)") (class "Default")
      (node (ref "IC4") (pin "1") (pinfunction "RO_1") (pintype "output"))
      (node (ref "R60") (pin "1") (pinfunction "1_1") (pintype "passive"))
    )
    (net (code "30") (name "Net-(INPUTSA-KL)") (class "Default")
      (node (ref "INPUTS") (pin "1") (pinfunction "KL_1") (pintype "passive"))
      (node (ref "R14") (pin "1") (pinfunction "1_1") (pintype "passive"))
      (node (ref "R76") (pin "1") (pinfunction "1_1") (pintype "passive"))
      (node (ref "R80") (pin "1") (pinfunction "1_1") (pintype "passive"))
      (node (ref "R84") (pin "1") (pinfunction "1_1") (pintype "passive"))
      (node (ref "R88") (pin "1") (pinfunction "1_1") (pintype "passive"))
    )
    (net (code "31") (name "Net-(INPUTSB-KL)") (class "Default")
      (node (ref "INPUTS") (pin "2") (pinfunction "KL_2") (pintype "passive"))
      (node (ref "R27") (pin "1") (pinfunction "1_1") (pintype "passive"))
    )
    (net (code "32") (name "Net-(INPUTSC-KL)") (class "Default")
      (node (ref "INPUTS") (pin "3") (pinfunction "KL_3") (pintype "passive"))
      (node (ref "R29") (pin "1") (pinfunction "1_1") (pintype "passive"))
    )
    (net (code "33") (name "Net-(INPUTSD-KL)") (class "Default")
      (node (ref "INPUTS") (pin "4") (pinfunction "KL_4") (pintype "passive"))
      (node (ref "R31") (pin "1") (pinfunction "1_1") (pintype "passive"))
    )
    (net (code "34") (name "Net-(INPUTSE-KL)") (class "Default")
      (node (ref "INPUTS") (pin "5") (pinfunction "KL_5") (pintype "passive"))
      (node (ref "R35") (pin "1") (pinfunction "1_1") (pintype "passive"))
    )
    (net (code "35") (name "Net-(INPUTSF-KL)") (class "Default")
      (node (ref "INPUTS") (pin "6") (pinfunction "KL_6") (pintype "passive"))
      (node (ref "R39") (pin "1") (pinfunction "1_1") (pintype "passive"))
    )
    (net (code "36") (name "Net-(J1B-S)") (class "Default")
      (node (ref "J1") (pin "2") (pinfunction "S_2") (pintype "passive"))
      (node (ref "R54") (pin "1") (pinfunction "1_1") (pintype "passive"))
    )
    (net (code "37") (name "Net-(LD1-PadA)") (class "Default")
      (node (ref "LD1") (pin "A") (pinfunction "A_A") (pintype "passive"))
      (node (ref "R74") (pin "2") (pinfunction "2_2") (pintype "passive"))
    )
    (net (code "38") (name "Net-(LD2-PadA)") (class "Default")
      (node (ref "LD2") (pin "A") (pinfunction "A_A") (pintype "passive"))
      (node (ref "R78") (pin "2") (pinfunction "2_2") (pintype "passive"))
    )
    (net (code "39") (name "Net-(LD3-PadA)") (class "Default")
      (node (ref "LD3") (pin "A") (pinfunction "A_A") (pintype "passive"))
      (node (ref "R82") (pin "2") (pinfunction "2_2") (pintype "passive"))
    )
    (net (code "40") (name "Net-(LD4-PadA)") (class "Default")
      (node (ref "LD4") (pin "A") (pinfunction "A_A") (pintype "passive"))
      (node (ref "R86") (pin "2") (pinfunction "2_2") (pintype "passive"))
    )
    (net (code "41") (name "Net-(LD5-PadA)") (class "Default")
      (node (ref "LD5") (pin "A") (pinfunction "A_A") (pintype "passive"))
      (node (ref "R45") (pin "2") (pinfunction "2_2") (pintype "passive"))
    )
    (net (code "42") (name "Net-(LD6-PadA)") (class "Default")
      (node (ref "LD6") (pin "A") (pinfunction "A_A") (pintype "passive"))
      (node (ref "R90") (pin "2") (pinfunction "2_2") (pintype "passive"))
    )
    (net (code "43") (name "Net-(LD7-PadA)") (class "Default")
      (node (ref "LD7") (pin "A") (pinfunction "A_A") (pintype "passive"))
      (node (ref "R4") (pin "2") (pinfunction "2_2") (pintype "passive"))
    )
    (net (code "44") (name "Net-(OK1-A)") (class "Default")
      (node (ref "OK1") (pin "1") (pinfunction "A_1") (pintype "passive"))
      (node (ref "R2") (pin "1") (pinfunction "1_1") (pintype "passive"))
    )
    (net (code "45") (name "Net-(OK1-A1)") (class "Default")
      (node (ref "OK1") (pin "4") (pinfunction "A1_4") (pintype "passive"))
      (node (ref "R12") (pin "2") (pinfunction "2_2") (pintype "passive"))
      (node (ref "T1") (pin "G") (pinfunction "G_G") (pintype "passive"))
    )
    (net (code "46") (name "Net-(OK1-A2)") (class "Default")
      (node (ref "OK1") (pin "6") (pinfunction "A2_6") (pintype "passive"))
      (node (ref "R15") (pin "2") (pinfunction "2_2") (pintype "passive"))
    )
    (net (code "47") (name "Net-(OK2-A)") (class "Default")
      (node (ref "OK2") (pin "1") (pinfunction "A_1") (pintype "passive"))
      (node (ref "R7") (pin "1") (pinfunction "1_1") (pintype "passive"))
    )
    (net (code "48") (name "Net-(OK2-A1)") (class "Default")
      (node (ref "OK2") (pin "4") (pinfunction "A1_4") (pintype "passive"))
      (node (ref "R8") (pin "2") (pinfunction "2_2") (pintype "passive"))
      (node (ref "T2") (pin "G") (pinfunction "G_G") (pintype "passive"))
    )
    (net (code "49") (name "Net-(OK2-A2)") (class "Default")
      (node (ref "OK2") (pin "6") (pinfunction "A2_6") (pintype "passive"))
      (node (ref "R9") (pin "2") (pinfunction "2_2") (pintype "passive"))
    )
    (net (code "50") (name "Net-(OK3-A)") (class "Default")
      (node (ref "OK3") (pin "1") (pinfunction "A_1") (pintype "passive"))
      (node (ref "R17") (pin "1") (pinfunction "1_1") (pintype "passive"))
    )
    (net (code "51") (name "Net-(OK3-A1)") (class "Default")
      (node (ref "OK3") (pin "4") (pinfunction "A1_4") (pintype "passive"))
      (node (ref "R18") (pin "2") (pinfunction "2_2") (pintype "passive"))
      (node (ref "T3") (pin "G") (pinfunction "G_G") (pintype "passive"))
    )
    (net (code "52") (name "Net-(OK3-A2)") (class "Default")
      (node (ref "OK3") (pin "6") (pinfunction "A2_6") (pintype "passive"))
      (node (ref "R20") (pin "2") (pinfunction "2_2") (pintype "passive"))
    )
    (net (code "53") (name "Net-(OK4-A)") (class "Default")
      (node (ref "OK4") (pin "1") (pinfunction "A_1") (pintype "passive"))
      (node (ref "R24") (pin "1") (pinfunction "1_1") (pintype "passive"))
    )
    (net (code "54") (name "Net-(OK4-A1)") (class "Default")
      (node (ref "OK4") (pin "4") (pinfunction "A1_4") (pintype "passive"))
      (node (ref "R25") (pin "2") (pinfunction "2_2") (pintype "passive"))
      (node (ref "T4") (pin "G") (pinfunction "G_G") (pintype "passive"))
    )
    (net (code "55") (name "Net-(OK4-A2)") (class "Default")
      (node (ref "OK4") (pin "6") (pinfunction "A2_6") (pintype "passive"))
      (node (ref "R26") (pin "2") (pinfunction "2_2") (pintype "passive"))
    )
    (net (code "56") (name "Net-(OK5-A)") (class "Default")
      (node (ref "OK5") (pin "1") (pinfunction "A_1") (pintype "passive"))
      (node (ref "R34") (pin "1") (pinfunction "1_1") (pintype "passive"))
    )
    (net (code "57") (name "Net-(OK5-A1)") (class "Default")
      (node (ref "OK5") (pin "4") (pinfunction "A1_4") (pintype "passive"))
      (node (ref "R36") (pin "2") (pinfunction "2_2") (pintype "passive"))
      (node (ref "T5") (pin "G") (pinfunction "G_G") (pintype "passive"))
    )
    (net (code "58") (name "Net-(OK5-A2)") (class "Default")
      (node (ref "OK5") (pin "6") (pinfunction "A2_6") (pintype "passive"))
      (node (ref "R37") (pin "2") (pinfunction "2_2") (pintype "passive"))
    )
    (net (code "59") (name "Net-(OK6-A)") (class "Default")
      (node (ref "OK6") (pin "1") (pinfunction "A_1") (pintype "passive"))
      (node (ref "R16") (pin "1") (pinfunction "1_1") (pintype "passive"))
    )
    (net (code "60") (name "Net-(OK6-A1)") (class "Default")
      (node (ref "OK6") (pin "4") (pinfunction "A1_4") (pintype "passive"))
      (node (ref "R19") (pin "2") (pinfunction "2_2") (pintype "passive"))
      (node (ref "T6") (pin "G") (pinfunction "G_G") (pintype "passive"))
    )
    (net (code "61") (name "Net-(OK6-A2)") (class "Default")
      (node (ref "OK6") (pin "6") (pinfunction "A2_6") (pintype "passive"))
      (node (ref "R21") (pin "2") (pinfunction "2_2") (pintype "passive"))
    )
    (net (code "62") (name "Net-(OK7-A)") (class "Default")
      (node (ref "OK7") (pin "1") (pinfunction "A_1") (pintype "passive"))
      (node (ref "R50") (pin "1") (pinfunction "1_1") (pintype "passive"))
    )
    (net (code "63") (name "Net-(OK7-A1)") (class "Default")
      (node (ref "OK7") (pin "4") (pinfunction "A1_4") (pintype "passive"))
      (node (ref "R51") (pin "2") (pinfunction "2_2") (pintype "passive"))
      (node (ref "T7") (pin "G") (pinfunction "G_G") (pintype "passive"))
    )
    (net (code "64") (name "Net-(OK7-A2)") (class "Default")
      (node (ref "OK7") (pin "6") (pinfunction "A2_6") (pintype "passive"))
      (node (ref "R62") (pin "2") (pinfunction "2_2") (pintype "passive"))
    )
    (net (code "65") (name "Net-(OK8-A)") (class "Default")
      (node (ref "OK8") (pin "1") (pinfunction "A_1") (pintype "passive"))
      (node (ref "R63") (pin "1") (pinfunction "1_1") (pintype "passive"))
    )
    (net (code "66") (name "Net-(OK8-A1)") (class "Default")
      (node (ref "OK8") (pin "4") (pinfunction "A1_4") (pintype "passive"))
      (node (ref "R64") (pin "2") (pinfunction "2_2") (pintype "passive"))
      (node (ref "T8") (pin "G") (pinfunction "G_G") (pintype "passive"))
    )
    (net (code "67") (name "Net-(OK8-A2)") (class "Default")
      (node (ref "OK8") (pin "6") (pinfunction "A2_6") (pintype "passive"))
      (node (ref "R65") (pin "2") (pinfunction "2_2") (pintype "passive"))
    )
    (net (code "68") (name "Net-(OK9-A)") (class "Default")
      (node (ref "OK9") (pin "1") (pinfunction "A_1") (pintype "passive"))
      (node (ref "R66") (pin "1") (pinfunction "1_1") (pintype "passive"))
    )
    (net (code "69") (name "Net-(OK9-A1)") (class "Default")
      (node (ref "OK9") (pin "4") (pinfunction "A1_4") (pintype "passive"))
      (node (ref "R67") (pin "2") (pinfunction "2_2") (pintype "passive"))
      (node (ref "T9") (pin "G") (pinfunction "G_G") (pintype "passive"))
    )
    (net (code "70") (name "Net-(OK9-A2)") (class "Default")
      (node (ref "OK9") (pin "6") (pinfunction "A2_6") (pintype "passive"))
      (node (ref "R68") (pin "2") (pinfunction "2_2") (pintype "passive"))
    )
    (net (code "71") (name "Net-(OK10-A)") (class "Default")
      (node (ref "OK10") (pin "1") (pinfunction "A_1") (pintype "passive"))
      (node (ref "R69") (pin "1") (pinfunction "1_1") (pintype "passive"))
    )
    (net (code "72") (name "Net-(OK10-A1)") (class "Default")
      (node (ref "OK10") (pin "4") (pinfunction "A1_4") (pintype "passive"))
      (node (ref "R70") (pin "2") (pinfunction "2_2") (pintype "passive"))
      (node (ref "T10") (pin "G") (pinfunction "G_G") (pintype "passive"))
    )
    (net (code "73") (name "Net-(OK10-A2)") (class "Default")
      (node (ref "OK10") (pin "6") (pinfunction "A2_6") (pintype "passive"))
      (node (ref "R71") (pin "2") (pinfunction "2_2") (pintype "passive"))
    )
    (net (code "74") (name "Net-(OK12-A)") (class "Default")
      (node (ref "OK12") (pin "1") (pinfunction "A_1") (pintype "passive"))
      (node (ref "Q1") (pin "C") (pinfunction "C_C") (pintype "passive"))
    )
    (net (code "75") (name "Net-(OK12-C)") (class "Default")
      (node (ref "B1") (pin "-") (pinfunction "-_-") (pintype "passive"))
      (node (ref "C21") (pin "2") (pinfunction "2_2") (pintype "passive"))
      (node (ref "D4") (pin "A") (pinfunction "A_A") (pintype "passive"))
      (node (ref "OK12") (pin "2") (pinfunction "C_2") (pintype "passive"))
      (node (ref "R55") (pin "1") (pinfunction "1_1") (pintype "passive"))
    )
    (net (code "76") (name "Net-(OK13-A)") (class "Default")
      (node (ref "LD1") (pin "C") (pinfunction "C_C") (pintype "passive"))
      (node (ref "OK13") (pin "1") (pinfunction "A_1") (pintype "passive"))
    )
    (net (code "77") (name "Net-(OK13-C)") (class "Default")
      (node (ref "OK13") (pin "2") (pinfunction "C_2") (pintype "passive"))
      (node (ref "R30") (pin "2") (pinfunction "2_2") (pintype "passive"))
    )
    (net (code "78") (name "Net-(OK14-A)") (class "Default")
      (node (ref "LD2") (pin "C") (pinfunction "C_C") (pintype "passive"))
      (node (ref "OK14") (pin "1") (pinfunction "A_1") (pintype "passive"))
    )
    (net (code "79") (name "Net-(OK14-C)") (class "Default")
      (node (ref "OK14") (pin "2") (pinfunction "C_2") (pintype "passive"))
      (node (ref "R33") (pin "2") (pinfunction "2_2") (pintype "passive"))
    )
    (net (code "80") (name "Net-(OK15-A)") (class "Default")
      (node (ref "LD3") (pin "C") (pinfunction "C_C") (pintype "passive"))
      (node (ref "OK15") (pin "1") (pinfunction "A_1") (pintype "passive"))
    )
    (net (code "81") (name "Net-(OK15-C)") (class "Default")
      (node (ref "OK15") (pin "2") (pinfunction "C_2") (pintype "passive"))
      (node (ref "R38") (pin "2") (pinfunction "2_2") (pintype "passive"))
    )
    (net (code "82") (name "Net-(OK16-A)") (class "Default")
      (node (ref "LD4") (pin "C") (pinfunction "C_C") (pintype "passive"))
      (node (ref "OK16") (pin "1") (pinfunction "A_1") (pintype "passive"))
    )
    (net (code "83") (name "Net-(OK16-C)") (class "Default")
      (node (ref "OK16") (pin "2") (pinfunction "C_2") (pintype "passive"))
      (node (ref "R40") (pin "2") (pinfunction "2_2") (pintype "passive"))
    )
    (net (code "84") (name "Net-(OUTS1-5A-KL)") (class "Default")
      (node (ref "OUTS1-5") (pin "1") (pinfunction "KL_1") (pintype "passive"))
      (node (ref "R20") (pin "1") (pinfunction "1_1") (pintype "passive"))
      (node (ref "R26") (pin "1") (pinfunction "1_1") (pintype "passive"))
      (node (ref "R37") (pin "1") (pinfunction "1_1") (pintype "passive"))
      (node (ref "R46") (pin "1") (pinfunction "1_1") (pintype "passive"))
      (node (ref "R9") (pin "1") (pinfunction "1_1") (pintype "passive"))
      (node (ref "T1") (pin "A2") (pinfunction "A2_A2") (pintype "passive"))
      (node (ref "T2") (pin "A2") (pinfunction "A2_A2") (pintype "passive"))
      (node (ref "T3") (pin "A2") (pinfunction "A2_A2") (pintype "passive"))
      (node (ref "T4") (pin "A2") (pinfunction "A2_A2") (pintype "passive"))
      (node (ref "T5") (pin "A2") (pinfunction "A2_A2") (pintype "passive"))
    )
    (net (code "85") (name "Net-(OUTS1-5B-KL)") (class "Default")
      (node (ref "C1") (pin "2") (pinfunction "2_2") (pintype "passive"))
      (node (ref "OUTS1-5") (pin "2") (pinfunction "KL_2") (pintype "passive"))
      (node (ref "R12") (pin "1") (pinfunction "1_1") (pintype "passive"))
      (node (ref "T1") (pin "A1") (pinfunction "A1_A1") (pintype "passive"))
    )
    (net (code "86") (name "Net-(OUTS1-5C-KL)") (class "Default")
      (node (ref "OUTS1-5") (pin "3") (pinfunction "KL_3") (pintype "passive"))
      (node (ref "R8") (pin "1") (pinfunction "1_1") (pintype "passive"))
      (node (ref "T2") (pin "A1") (pinfunction "A1_A1") (pintype "passive"))
    )
    (net (code "87") (name "Net-(OUTS1-5D-KL)") (class "Default")
      (node (ref "OUTS1-5") (pin "4") (pinfunction "KL_4") (pintype "passive"))
      (node (ref "R18") (pin "1") (pinfunction "1_1") (pintype "passive"))
      (node (ref "T3") (pin "A1") (pinfunction "A1_A1") (pintype "passive"))
    )
    (net (code "88") (name "Net-(OUTS1-5E-KL)") (class "Default")
      (node (ref "OUTS1-5") (pin "5") (pinfunction "KL_5") (pintype "passive"))
      (node (ref "R25") (pin "1") (pinfunction "1_1") (pintype "passive"))
      (node (ref "T4") (pin "A1") (pinfunction "A1_A1") (pintype "passive"))
    )
    (net (code "89") (name "Net-(OUTS1-5F-KL)") (class "Default")
      (node (ref "OUTS1-5") (pin "6") (pinfunction "KL_6") (pintype "passive"))
      (node (ref "R36") (pin "1") (pinfunction "1_1") (pintype "passive"))
      (node (ref "T5") (pin "A1") (pinfunction "A1_A1") (pintype "passive"))
    )
    (net (code "90") (name "Net-(OUTS6-10A-KL)") (class "Default")
      (node (ref "OUTS6-10") (pin "1") (pinfunction "KL_1") (pintype "passive"))
      (node (ref "R21") (pin "1") (pinfunction "1_1") (pintype "passive"))
      (node (ref "R47") (pin "2") (pinfunction "2_2") (pintype "passive"))
      (node (ref "R65") (pin "1") (pinfunction "1_1") (pintype "passive"))
      (node (ref "R68") (pin "1") (pinfunction "1_1") (pintype "passive"))
      (node (ref "R71") (pin "1") (pinfunction "1_1") (pintype "passive"))
      (node (ref "T10") (pin "A2") (pinfunction "A2_A2") (pintype "passive"))
      (node (ref "T6") (pin "A2") (pinfunction "A2_A2") (pintype "passive"))
      (node (ref "T7") (pin "A2") (pinfunction "A2_A2") (pintype "passive"))
      (node (ref "T8") (pin "A2") (pinfunction "A2_A2") (pintype "passive"))
      (node (ref "T9") (pin "A2") (pinfunction "A2_A2") (pintype "passive"))
    )
    (net (code "91") (name "Net-(OUTS6-10B-KL)") (class "Default")
      (node (ref "C2") (pin "2") (pinfunction "2_2") (pintype "passive"))
      (node (ref "OUTS6-10") (pin "2") (pinfunction "KL_2") (pintype "passive"))
      (node (ref "R51") (pin "1") (pinfunction "1_1") (pintype "passive"))
      (node (ref "T7") (pin "A1") (pinfunction "A1_A1") (pintype "passive"))
    )
    (net (code "92") (name "Net-(OUTS6-10C-KL)") (class "Default")
      (node (ref "OUTS6-10") (pin "3") (pinfunction "KL_3") (pintype "passive"))
      (node (ref "R19") (pin "1") (pinfunction "1_1") (pintype "passive"))
      (node (ref "T6") (pin "A1") (pinfunction "A1_A1") (pintype "passive"))
    )
    (net (code "93") (name "Net-(OUTS6-10D-KL)") (class "Default")
      (node (ref "OUTS6-10") (pin "4") (pinfunction "KL_4") (pintype "passive"))
      (node (ref "R64") (pin "1") (pinfunction "1_1") (pintype "passive"))
      (node (ref "T8") (pin "A1") (pinfunction "A1_A1") (pintype "passive"))
    )
    (net (code "94") (name "Net-(OUTS6-10E-KL)") (class "Default")
      (node (ref "OUTS6-10") (pin "5") (pinfunction "KL_5") (pintype "passive"))
      (node (ref "R67") (pin "1") (pinfunction "1_1") (pintype "passive"))
      (node (ref "T9") (pin "A1") (pinfunction "A1_A1") (pintype "passive"))
    )
    (net (code "95") (name "Net-(OUTS6-10F-KL)") (class "Default")
      (node (ref "OUTS6-10") (pin "6") (pinfunction "KL_6") (pintype "passive"))
      (node (ref "R70") (pin "1") (pinfunction "1_1") (pintype "passive"))
      (node (ref "T10") (pin "A1") (pinfunction "A1_A1") (pintype "passive"))
    )
    (net (code "96") (name "Net-(POWERA-KL)") (class "Default")
      (node (ref "B2") (pin "AC1") (pinfunction "AC1_AC1") (pintype "passive"))
      (node (ref "POWER") (pin "1") (pinfunction "KL_1") (pintype "passive"))
    )
    (net (code "97") (name "Net-(POWERB-KL)") (class "Default")
      (node (ref "B2") (pin "AC2") (pinfunction "AC2_AC2") (pintype "passive"))
      (node (ref "POWER") (pin "2") (pinfunction "KL_2") (pintype "passive"))
    )
    (net (code "98") (name "Net-(Q1-PadE)") (class "Default")
      (node (ref "Q1") (pin "E") (pinfunction "E_E") (pintype "passive"))
      (node (ref "R56") (pin "1") (pinfunction "1_1") (pintype "passive"))
    )
    (net (code "99") (name "Net-(R1-Pad1)") (class "Default")
      (node (ref "R1") (pin "1") (pinfunction "1_1") (pintype "passive"))
      (node (ref "T11") (pin "B") (pinfunction "B_B") (pintype "passive"))
    )
    (net (code "100") (name "Net-(R3-Pad1)") (class "Default")
      (node (ref "R3") (pin "1") (pinfunction "1_1") (pintype "passive"))
      (node (ref "T12") (pin "B") (pinfunction "B_B") (pintype "passive"))
    )
    (net (code "101") (name "Net-(R11-Pad1)") (class "Default")
      (node (ref "R11") (pin "1") (pinfunction "1_1") (pintype "passive"))
      (node (ref "R13") (pin "2") (pinfunction "2_2") (pintype "passive"))
    )
    (net (code "102") (name "Net-(R13-Pad1)") (class "Default")
      (node (ref "R13") (pin "1") (pinfunction "1_1") (pintype "passive"))
      (node (ref "R14") (pin "2") (pinfunction "2_2") (pintype "passive"))
    )
    (net (code "103") (name "Net-(R22-Pad1)") (class "Default")
      (node (ref "R22") (pin "1") (pinfunction "1_1") (pintype "passive"))
      (node (ref "R23") (pin "2") (pinfunction "2_2") (pintype "passive"))
    )
    (net (code "104") (name "Net-(R23-Pad1)") (class "Default")
      (node (ref "R23") (pin "1") (pinfunction "1_1") (pintype "passive"))
      (node (ref "R27") (pin "2") (pinfunction "2_2") (pintype "passive"))
    )
    (net (code "105") (name "Net-(R29-Pad2)") (class "Default")
      (node (ref "R29") (pin "2") (pinfunction "2_2") (pintype "passive"))
      (node (ref "R73") (pin "1") (pinfunction "1_1") (pintype "passive"))
    )
    (net (code "106") (name "Net-(R30-Pad1)") (class "Default")
      (node (ref "R30") (pin "1") (pinfunction "1_1") (pintype "passive"))
      (node (ref "R75") (pin "2") (pinfunction "2_2") (pintype "passive"))
    )
    (net (code "107") (name "Net-(R31-Pad2)") (class "Default")
      (node (ref "R31") (pin "2") (pinfunction "2_2") (pintype "passive"))
      (node (ref "R77") (pin "1") (pinfunction "1_1") (pintype "passive"))
    )
    (net (code "108") (name "Net-(R33-Pad1)") (class "Default")
      (node (ref "R33") (pin "1") (pinfunction "1_1") (pintype "passive"))
      (node (ref "R79") (pin "2") (pinfunction "2_2") (pintype "passive"))
    )
    (net (code "109") (name "Net-(R35-Pad2)") (class "Default")
      (node (ref "R35") (pin "2") (pinfunction "2_2") (pintype "passive"))
      (node (ref "R81") (pin "1") (pinfunction "1_1") (pintype "passive"))
    )
    (net (code "110") (name "Net-(R38-Pad1)") (class "Default")
      (node (ref "R38") (pin "1") (pinfunction "1_1") (pintype "passive"))
      (node (ref "R83") (pin "2") (pinfunction "2_2") (pintype "passive"))
    )
    (net (code "111") (name "Net-(R39-Pad2)") (class "Default")
      (node (ref "R39") (pin "2") (pinfunction "2_2") (pintype "passive"))
      (node (ref "R85") (pin "1") (pinfunction "1_1") (pintype "passive"))
    )
    (net (code "112") (name "Net-(R40-Pad1)") (class "Default")
      (node (ref "R40") (pin "1") (pinfunction "1_1") (pintype "passive"))
      (node (ref "R87") (pin "2") (pinfunction "2_2") (pintype "passive"))
    )
    (net (code "113") (name "Net-(R73-Pad2)") (class "Default")
      (node (ref "R73") (pin "2") (pinfunction "2_2") (pintype "passive"))
      (node (ref "R74") (pin "1") (pinfunction "1_1") (pintype "passive"))
    )
    (net (code "114") (name "Net-(R75-Pad1)") (class "Default")
      (node (ref "R75") (pin "1") (pinfunction "1_1") (pintype "passive"))
      (node (ref "R76") (pin "2") (pinfunction "2_2") (pintype "passive"))
    )
    (net (code "115") (name "Net-(R77-Pad2)") (class "Default")
      (node (ref "R77") (pin "2") (pinfunction "2_2") (pintype "passive"))
      (node (ref "R78") (pin "1") (pinfunction "1_1") (pintype "passive"))
    )
    (net (code "116") (name "Net-(R79-Pad1)") (class "Default")
      (node (ref "R79") (pin "1") (pinfunction "1_1") (pintype "passive"))
      (node (ref "R80") (pin "2") (pinfunction "2_2") (pintype "passive"))
    )
    (net (code "117") (name "Net-(R81-Pad2)") (class "Default")
      (node (ref "R81") (pin "2") (pinfunction "2_2") (pintype "passive"))
      (node (ref "R82") (pin "1") (pinfunction "1_1") (pintype "passive"))
    )
    (net (code "118") (name "Net-(R83-Pad1)") (class "Default")
      (node (ref "R83") (pin "1") (pinfunction "1_1") (pintype "passive"))
      (node (ref "R84") (pin "2") (pinfunction "2_2") (pintype "passive"))
    )
    (net (code "119") (name "Net-(R85-Pad2)") (class "Default")
      (node (ref "R85") (pin "2") (pinfunction "2_2") (pintype "passive"))
      (node (ref "R86") (pin "1") (pinfunction "1_1") (pintype "passive"))
    )
    (net (code "120") (name "Net-(R87-Pad1)") (class "Default")
      (node (ref "R87") (pin "1") (pinfunction "1_1") (pintype "passive"))
      (node (ref "R88") (pin "2") (pinfunction "2_2") (pintype "passive"))
    )
    (net (code "121") (name "Net-(U1-TXD)") (class "Default")
      (node (ref "R49") (pin "1") (pinfunction "1_1") (pintype "passive"))
      (node (ref "U1") (pin "35") (pinfunction "TXD_35") (pintype "bidirectional"))
    )
    (net (code "122") (name "Net-(U2-RXI)") (class "Default")
      (node (ref "R92") (pin "1") (pinfunction "1_1") (pintype "passive"))
      (node (ref "U2") (pin "3") (pinfunction "RXI_3") (pintype "bidirectional"))
    )
    (net (code "123") (name "Net-(U2-TXO)") (class "Default")
      (node (ref "R91") (pin "1") (pinfunction "1_1") (pintype "passive"))
      (node (ref "U2") (pin "2") (pinfunction "TXO_2") (pintype "bidirectional"))
    )
    (net (code "124") (name "Net-(U2-UD+)") (class "Default")
      (node (ref "U2") (pin "5") (pinfunction "UD+_5") (pintype "bidirectional"))
      (node (ref "USB") (pin "3") (pinfunction "D+_3") (pintype "bidirectional"))
    )
    (net (code "125") (name "Net-(U2-UD-)") (class "Default")
      (node (ref "U2") (pin "6") (pinfunction "UD-_6") (pintype "bidirectional"))
      (node (ref "USB") (pin "2") (pinfunction "D-_2") (pintype "bidirectional"))
    )
    (net (code "126") (name "Net-(U2-V3)") (class "Default")
      (node (ref "C23") (pin "2") (pinfunction "2_2") (pintype "passive"))
      (node (ref "U2") (pin "4") (pinfunction "V3_4") (pintype "bidirectional"))
    )
    (net (code "127") (name "Net-(U2-VCC)") (class "Default")
      (node (ref "C22") (pin "1") (pinfunction "1_1") (pintype "passive"))
      (node (ref "C24") (pin "+") (pinfunction "+_+") (pintype "passive"))
      (node (ref "D1") (pin "A") (pinfunction "A_A") (pintype "passive"))
      (node (ref "U2") (pin "16") (pinfunction "VCC_16") (pintype "bidirectional"))
      (node (ref "USB") (pin "1") (pinfunction "+5V_1") (pintype "bidirectional"))
    )
    (net (code "128") (name "OUT1") (class "Default")
      (node (ref "R2") (pin "2") (pinfunction "2_2") (pintype "passive"))
      (node (ref "U1") (pin "10") (pinfunction "IO25_10") (pintype "bidirectional"))
    )
    (net (code "129") (name "OUT2") (class "Default")
      (node (ref "R7") (pin "2") (pinfunction "2_2") (pintype "passive"))
      (node (ref "U1") (pin "13") (pinfunction "SCK_H/IO14_13") (pintype "bidirectional"))
    )
    (net (code "130") (name "OUT3") (class "Default")
      (node (ref "R17") (pin "2") (pinfunction "2_2") (pintype "passive"))
      (node (ref "U1") (pin "11") (pinfunction "IO26_11") (pintype "bidirectional"))
    )
    (net (code "131") (name "OUT4") (class "Default")
      (node (ref "R24") (pin "2") (pinfunction "2_2") (pintype "passive"))
      (node (ref "U1") (pin "30") (pinfunction "SCK_V/IO18_30") (pintype "bidirectional"))
    )
    (net (code "132") (name "OUT5") (class "Default")
      (node (ref "R34") (pin "2") (pinfunction "2_2") (pintype "passive"))
      (node (ref "U1") (pin "31") (pinfunction "MISO_V/IO19_31") (pintype "bidirectional"))
    )
    (net (code "133") (name "OUT6") (class "Default")
      (node (ref "R50") (pin "2") (pinfunction "2_2") (pintype "passive"))
      (node (ref "U1") (pin "14") (pinfunction "MISO_H/IO12_14") (pintype "bidirectional"))
    )
    (net (code "134") (name "OUT7") (class "Default")
      (node (ref "R16") (pin "2") (pinfunction "2_2") (pintype "passive"))
      (node (ref "R89") (pin "1") (pinfunction "1_1") (pintype "passive"))
      (node (ref "U1") (pin "23") (pinfunction "CS0_H/IO15_23") (pintype "bidirectional"))
    )
    (net (code "135") (name "OUT8") (class "Default")
      (node (ref "R63") (pin "2") (pinfunction "2_2") (pintype "passive"))
      (node (ref "U1") (pin "36") (pinfunction "IO22_36") (pintype "bidirectional"))
    )
    (net (code "136") (name "OUT9") (class "Default")
      (node (ref "R66") (pin "2") (pinfunction "2_2") (pintype "passive"))
      (node (ref "U1") (pin "37") (pinfunction "MOSI_V/IO23_37") (pintype "bidirectional"))
    )
    (net (code "137") (name "OUT10") (class "Default")
      (node (ref "R69") (pin "2") (pinfunction "2_2") (pintype "passive"))
      (node (ref "U1") (pin "33") (pinfunction "IO21_33") (pintype "bidirectional"))
    )
    (net (code "138") (name "PIR1") (class "Default")
      (node (ref "JP6") (pin "2") (pinfunction "2_2") (pintype "passive"))
      (node (ref "R54") (pin "2") (pinfunction "2_2") (pintype "passive"))
      (node (ref "R57") (pin "2") (pinfunction "2_2") (pintype "passive"))
      (node (ref "R58") (pin "1") (pinfunction "1_1") (pintype "passive"))
      (node (ref "U1") (pin "8") (pinfunction "XTAL_P/IO32_8") (pintype "bidirectional"))
    )
    (net (code "139") (name "RTS") (class "Default")
      (node (ref "R3") (pin "2") (pinfunction "2_2") (pintype "passive"))
      (node (ref "T11") (pin "E") (pinfunction "E_E") (pintype "passive"))
      (node (ref "U2") (pin "14") (pinfunction "~{RTS}_14") (pintype "bidirectional"))
    )
    (net (code "140") (name "RX") (class "Default")
      (node (ref "DEBUG") (pin "3") (pinfunction "3_3") (pintype "passive"))
      (node (ref "R91") (pin "2") (pinfunction "2_2") (pintype "passive"))
      (node (ref "U1") (pin "34") (pinfunction "RXD_34") (pintype "bidirectional"))
    )
    (net (code "141") (name "RX-2") (class "Default")
      (node (ref "JP5") (pin "1") (pinfunction "1_1") (pintype "passive"))
      (node (ref "R60") (pin "2") (pinfunction "2_2") (pintype "passive"))
      (node (ref "R61") (pin "2") (pinfunction "2_2") (pintype "passive"))
      (node (ref "U1") (pin "27") (pinfunction "IO16_27") (pintype "bidirectional"))
    )
    (net (code "142") (name "R{slash}W") (class "Default")
      (node (ref "IC4") (pin "2") (pinfunction "RE/_2") (pintype "input"))
      (node (ref "JP2") (pin "1") (pinfunction "1_1") (pintype "passive"))
      (node (ref "JP6") (pin "1") (pinfunction "1_1") (pintype "passive"))
      (node (ref "R52") (pin "2") (pinfunction "2_2") (pintype "passive"))
      (node (ref "U1") (pin "12") (pinfunction "IO27_12") (pintype "bidirectional"))
    )
    (net (code "143") (name "TX") (class "Default")
      (node (ref "DEBUG") (pin "2") (pinfunction "2_2") (pintype "passive"))
      (node (ref "R49") (pin "2") (pinfunction "2_2") (pintype "passive"))
      (node (ref "R92") (pin "2") (pinfunction "2_2") (pintype "passive"))
    )
    (net (code "144") (name "TX-2") (class "Default")
      (node (ref "JP1") (pin "1") (pinfunction "1_1") (pintype "passive"))
      (node (ref "JP2") (pin "3") (pinfunction "3_3") (pintype "passive"))
      (node (ref "JP5") (pin "2") (pinfunction "2_2") (pintype "passive"))
      (node (ref "R72") (pin "2") (pinfunction "2_2") (pintype "passive"))
      (node (ref "U1") (pin "28") (pinfunction "IO17_28") (pintype "bidirectional"))
    )
    (net (code "145") (name "unconnected-(U1-NC-Pad32)") (class "Default")
      (node (ref "U1") (pin "32") (pinfunction "NC_32") (pintype "bidirectional"))
    )
    (net (code "146") (name "unconnected-(U1-SCK{slash}IO6-Pad20)") (class "Default")
      (node (ref "U1") (pin "20") (pinfunction "SCK/IO6_20") (pintype "bidirectional"))
    )
    (net (code "147") (name "unconnected-(U1-SCS{slash}IO11-Pad19)") (class "Default")
      (node (ref "U1") (pin "19") (pinfunction "SCS/IO11_19") (pintype "bidirectional"))
    )
    (net (code "148") (name "unconnected-(U1-SDI{slash}IO8-Pad22)") (class "Default")
      (node (ref "U1") (pin "22") (pinfunction "SDI/IO8_22") (pintype "bidirectional"))
    )
    (net (code "149") (name "unconnected-(U1-SDO{slash}IO7-Pad21)") (class "Default")
      (node (ref "U1") (pin "21") (pinfunction "SDO/IO7_21") (pintype "bidirectional"))
    )
    (net (code "150") (name "unconnected-(U1-SHD{slash}IO9-Pad17)") (class "Default")
      (node (ref "U1") (pin "17") (pinfunction "SHD/IO9_17") (pintype "bidirectional"))
    )
    (net (code "151") (name "unconnected-(U1-SWP{slash}IO10-Pad18)") (class "Default")
      (node (ref "U1") (pin "18") (pinfunction "SWP/IO10_18") (pintype "bidirectional"))
    )
    (net (code "152") (name "unconnected-(U2-R232-Pad15)") (class "Default")
      (node (ref "U2") (pin "15") (pinfunction "R232_15") (pintype "bidirectional"))
    )
    (net (code "153") (name "unconnected-(U2-~{CTS}-Pad9)") (class "Default")
      (node (ref "U2") (pin "9") (pinfunction "~{CTS}_9") (pintype "bidirectional"))
    )
    (net (code "154") (name "unconnected-(U2-~{DCD}-Pad12)") (class "Default")
      (node (ref "U2") (pin "12") (pinfunction "~{DCD}_12") (pintype "bidirectional"))
    )
    (net (code "155") (name "unconnected-(U2-~{DSR}-Pad10)") (class "Default")
      (node (ref "U2") (pin "10") (pinfunction "~{DSR}_10") (pintype "bidirectional"))
    )
    (net (code "156") (name "unconnected-(U2-~{RI}-Pad11)") (class "Default")
      (node (ref "U2") (pin "11") (pinfunction "~{RI}_11") (pintype "bidirectional"))
    )
    (net (code "157") (name "unconnected-(USB-ID-Pad4)") (class "Default")
      (node (ref "USB") (pin "4") (pinfunction "ID_4") (pintype "bidirectional"))
    )
  )
)
